# Receiver.net
KiCad netlist of a schematic drawn in EAGLE
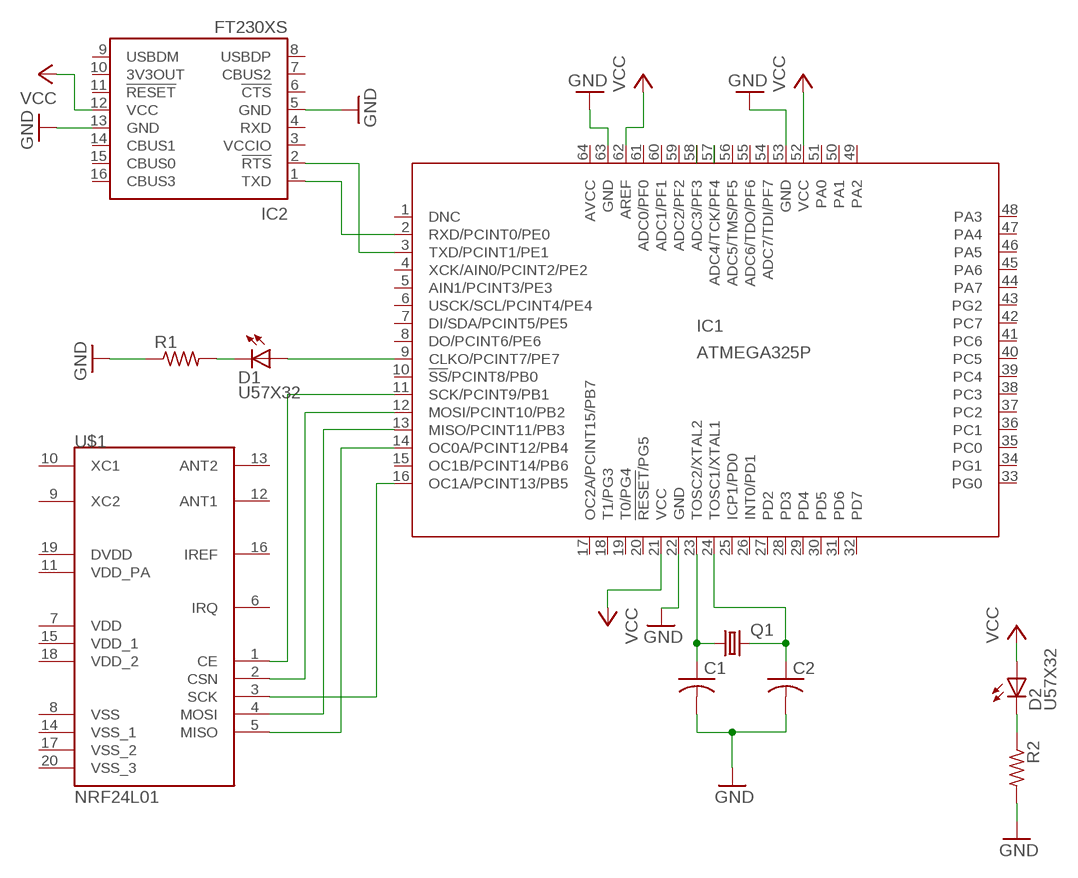
[diagram p0: schematic, sheet 1]

(export (version "E")
  (design (tool "Eeschema 10.0.6"))
  (components
    (comp (ref "C1")
      (value "C-US025-024X044")
      (footprint "eagle-import:C025-024X044")
      (libsource (lib "eagle-import") (part "C-US025-024X044"))
    )
    (comp (ref "C2")
      (value "C-US025-024X044")
      (footprint "eagle-import:C025-024X044")
      (libsource (lib "eagle-import") (part "C-US025-024X044"))
    )
    (comp (ref "D1")
      (value "U57X32")
      (footprint "eagle-import:U57X32")
      (libsource (lib "eagle-import") (part "U57X32"))
    )
    (comp (ref "D2")
      (value "U57X32")
      (footprint "eagle-import:U57X32")
      (libsource (lib "eagle-import") (part "U57X32"))
    )
    (comp (ref "IC1")
      (value "ATMEGA325P")
      (footprint "eagle-import:64M1")
      (fields (field (name "MPN") "ATMEGA325PV-10AU"))
      (libsource (lib "eagle-import") (part "ATMEGA325P"))
    )
    (comp (ref "IC2")
      (value "FT230XS")
      (footprint "eagle-import:SSOP16")
      (libsource (lib "eagle-import") (part "FT230XS"))
    )
    (comp (ref "Q1")
      (value "CRYSTALHC49S")
      (footprint "eagle-import:HC49_S")
      (libsource (lib "eagle-import") (part "CRYSTALHC49S"))
    )
    (comp (ref "R1")
      (value "R-US_0204/5")
      (footprint "eagle-import:0204_5")
      (libsource (lib "eagle-import") (part "R-US_0204/5"))
    )
    (comp (ref "R2")
      (value "R-US_0204/5")
      (footprint "eagle-import:0204_5")
      (libsource (lib "eagle-import") (part "R-US_0204/5"))
    )
    (comp (ref "U$1")
      (value "NRF24L01")
      (footprint "eagle-import:QFN20")
      (libsource (lib "eagle-import") (part "NRF24L01"))
    )
  )
  (nets
    (net (code "1") (name "/AVCC") (class "Default")
      (node (ref "IC1") (pin "64") (pinfunction "AVCC_64") (pintype "power_in"))
    )
    (net (code "2") (name "/VCCIO") (class "Default")
      (node (ref "IC2") (pin "3") (pinfunction "VCCIO_3") (pintype "power_in"))
    )
    (net (code "3") (name "GND") (class "Default")
      (node (ref "C1") (pin "2") (pinfunction "2_2") (pintype "passive"))
      (node (ref "C2") (pin "2") (pinfunction "2_2") (pintype "passive"))
      (node (ref "IC1") (pin "22") (pinfunction "GND_22") (pintype "power_in"))
      (node (ref "IC1") (pin "53") (pinfunction "GND_53") (pintype "power_in"))
      (node (ref "IC1") (pin "63") (pinfunction "GND_63") (pintype "power_in"))
      (node (ref "IC2") (pin "13") (pinfunction "GND_13") (pintype "power_in"))
      (node (ref "IC2") (pin "5") (pinfunction "GND_5") (pintype "power_in"))
      (node (ref "R1") (pin "1") (pinfunction "1_1") (pintype "passive"))
      (node (ref "R2") (pin "2") (pinfunction "2_2") (pintype "passive"))
    )
    (net (code "4") (name "Net-(D1-C)") (class "Default")
      (node (ref "D1") (pin "K") (pinfunction "C_K") (pintype "passive"))
      (node (ref "R1") (pin "2") (pinfunction "2_2") (pintype "passive"))
    )
    (net (code "5") (name "Net-(D2-C)") (class "Default")
      (node (ref "D2") (pin "K") (pinfunction "C_K") (pintype "passive"))
      (node (ref "R2") (pin "1") (pinfunction "1_1") (pintype "passive"))
    )
    (net (code "6") (name "Net-(IC1-CLKO{slash}PCINT7{slash}PE7)") (class "Default")
      (node (ref "D1") (pin "A") (pinfunction "A_A") (pintype "passive"))
      (node (ref "IC1") (pin "9") (pinfunction "CLKO/PCINT7/PE7_9") (pintype "bidirectional"))
    )
    (net (code "7") (name "Net-(IC1-MISO{slash}PCINT11{slash}PB3)") (class "Default")
      (node (ref "IC1") (pin "13") (pinfunction "MISO/PCINT11/PB3_13") (pintype "bidirectional"))
      (node (ref "U$1") (pin "4") (pinfunction "MOSI_4") (pintype "bidirectional"))
    )
    (net (code "8") (name "Net-(IC1-MOSI{slash}PCINT10{slash}PB2)") (class "Default")
      (node (ref "IC1") (pin "12") (pinfunction "MOSI/PCINT10/PB2_12") (pintype "bidirectional"))
      (node (ref "U$1") (pin "2") (pinfunction "CSN_2") (pintype "bidirectional"))
    )
    (net (code "9") (name "Net-(IC1-OC0A{slash}PCINT12{slash}PB4)") (class "Default")
      (node (ref "IC1") (pin "14") (pinfunction "OC0A/PCINT12/PB4_14") (pintype "bidirectional"))
      (node (ref "U$1") (pin "5") (pinfunction "MISO_5") (pintype "bidirectional"))
    )
    (net (code "10") (name "Net-(IC1-OC1A{slash}PCINT13{slash}PB5)") (class "Default")
      (node (ref "IC1") (pin "16") (pinfunction "OC1A/PCINT13/PB5_16") (pintype "bidirectional"))
      (node (ref "U$1") (pin "3") (pinfunction "SCK_3") (pintype "bidirectional"))
    )
    (net (code "11") (name "Net-(IC1-RXD{slash}PCINT0{slash}PE0)") (class "Default")
      (node (ref "IC1") (pin "2") (pinfunction "RXD/PCINT0/PE0_2") (pintype "bidirectional"))
      (node (ref "IC2") (pin "1") (pinfunction "TXD_1") (pintype "output"))
    )
    (net (code "12") (name "Net-(IC1-SCK{slash}PCINT9{slash}PB1)") (class "Default")
      (node (ref "IC1") (pin "11") (pinfunction "SCK/PCINT9/PB1_11") (pintype "bidirectional"))
      (node (ref "U$1") (pin "1") (pinfunction "CE_1") (pintype "bidirectional"))
    )
    (net (code "13") (name "Net-(IC1-TOSC1{slash}XTAL1)") (class "Default")
      (node (ref "C2") (pin "1") (pinfunction "1_1") (pintype "passive"))
      (node (ref "IC1") (pin "24") (pinfunction "TOSC1/XTAL1_24") (pintype "input"))
      (node (ref "Q1") (pin "2") (pinfunction "2_2") (pintype "passive"))
    )
    (net (code "14") (name "Net-(IC1-TOSC2{slash}XTAL2)") (class "Default")
      (node (ref "C1") (pin "1") (pinfunction "1_1") (pintype "passive"))
      (node (ref "IC1") (pin "23") (pinfunction "TOSC2/XTAL2_23") (pintype "output"))
      (node (ref "Q1") (pin "1") (pinfunction "1_1") (pintype "passive"))
    )
    (net (code "15") (name "Net-(IC1-TXD{slash}PCINT1{slash}PE1)") (class "Default")
      (node (ref "IC1") (pin "3") (pinfunction "TXD/PCINT1/PE1_3") (pintype "bidirectional"))
      (node (ref "IC2") (pin "2") (pinfunction "~{RTS}_2") (pintype "output"))
    )
    (net (code "16") (name "VCC") (class "Default")
      (node (ref "D2") (pin "A") (pinfunction "A_A") (pintype "passive"))
      (node (ref "IC1") (pin "21") (pinfunction "VCC_21") (pintype "power_in"))
      (node (ref "IC1") (pin "52") (pinfunction "VCC_52") (pintype "power_in"))
      (node (ref "IC1") (pin "62") (pinfunction "AREF_62") (pintype "input"))
      (node (ref "IC2") (pin "12") (pinfunction "VCC_12") (pintype "power_in"))
    )
    (net (code "17") (name "unconnected-(IC1-ADC0{slash}PF0-Pad61)") (class "Default")
      (node (ref "IC1") (pin "61") (pinfunction "ADC0/PF0_61") (pintype "bidirectional"))
    )
    (net (code "18") (name "unconnected-(IC1-ADC1{slash}PF1-Pad60)") (class "Default")
      (node (ref "IC1") (pin "60") (pinfunction "ADC1/PF1_60") (pintype "bidirectional"))
    )
    (net (code "19") (name "unconnected-(IC1-ADC2{slash}PF2-Pad59)") (class "Default")
      (node (ref "IC1") (pin "59") (pinfunction "ADC2/PF2_59") (pintype "bidirectional"))
    )
    (net (code "20") (name "unconnected-(IC1-ADC3{slash}PF3-Pad58)") (class "Default")
      (node (ref "IC1") (pin "58") (pinfunction "ADC3/PF3_58") (pintype "bidirectional"))
    )
    (net (code "21") (name "unconnected-(IC1-ADC4{slash}TCK{slash}PF4-Pad57)") (class "Default")
      (node (ref "IC1") (pin "57") (pinfunction "ADC4/TCK/PF4_57") (pintype "bidirectional"))
    )
    (net (code "22") (name "unconnected-(IC1-ADC5{slash}TMS{slash}PF5-Pad56)") (class "Default")
      (node (ref "IC1") (pin "56") (pinfunction "ADC5/TMS/PF5_56") (pintype "bidirectional"))
    )
    (net (code "23") (name "unconnected-(IC1-ADC6{slash}TDO{slash}PF6-Pad55)") (class "Default")
      (node (ref "IC1") (pin "55") (pinfunction "ADC6/TDO/PF6_55") (pintype "bidirectional"))
    )
    (net (code "24") (name "unconnected-(IC1-ADC7{slash}TDI{slash}PF7-Pad54)") (class "Default")
      (node (ref "IC1") (pin "54") (pinfunction "ADC7/TDI/PF7_54") (pintype "bidirectional"))
    )
    (net (code "25") (name "unconnected-(IC1-AIN1{slash}PCINT3{slash}PE3-Pad5)") (class "Default")
      (node (ref "IC1") (pin "5") (pinfunction "AIN1/PCINT3/PE3_5") (pintype "bidirectional"))
    )
    (net (code "26") (name "unconnected-(IC1-DI{slash}SDA{slash}PCINT5{slash}PE5-Pad7)") (class "Default")
      (node (ref "IC1") (pin "7") (pinfunction "DI/SDA/PCINT5/PE5_7") (pintype "bidirectional"))
    )
    (net (code "27") (name "unconnected-(IC1-DNC-Pad1)") (class "Default")
      (node (ref "IC1") (pin "1") (pinfunction "DNC_1") (pintype "input"))
    )
    (net (code "28") (name "unconnected-(IC1-DO{slash}PCINT6{slash}PE6-Pad8)") (class "Default")
      (node (ref "IC1") (pin "8") (pinfunction "DO/PCINT6/PE6_8") (pintype "bidirectional"))
    )
    (net (code "29") (name "unconnected-(IC1-ICP1{slash}PD0-Pad25)") (class "Default")
      (node (ref "IC1") (pin "25") (pinfunction "ICP1/PD0_25") (pintype "bidirectional"))
    )
    (net (code "30") (name "unconnected-(IC1-INT0{slash}PD1-Pad26)") (class "Default")
      (node (ref "IC1") (pin "26") (pinfunction "INT0/PD1_26") (pintype "bidirectional"))
    )
    (net (code "31") (name "unconnected-(IC1-OC1B{slash}PCINT14{slash}PB6-Pad15)") (class "Default")
      (node (ref "IC1") (pin "15") (pinfunction "OC1B/PCINT14/PB6_15") (pintype "bidirectional"))
    )
    (net (code "32") (name "unconnected-(IC1-OC2A{slash}PCINT15{slash}PB7-Pad17)") (class "Default")
      (node (ref "IC1") (pin "17") (pinfunction "OC2A/PCINT15/PB7_17") (pintype "bidirectional"))
    )
    (net (code "33") (name "unconnected-(IC1-PA0-Pad51)") (class "Default")
      (node (ref "IC1") (pin "51") (pinfunction "PA0_51") (pintype "bidirectional"))
    )
    (net (code "34") (name "unconnected-(IC1-PA1-Pad50)") (class "Default")
      (node (ref "IC1") (pin "50") (pinfunction "PA1_50") (pintype "bidirectional"))
    )
    (net (code "35") (name "unconnected-(IC1-PA2-Pad49)") (class "Default")
      (node (ref "IC1") (pin "49") (pinfunction "PA2_49") (pintype "bidirectional"))
    )
    (net (code "36") (name "unconnected-(IC1-PA3-Pad48)") (class "Default")
      (node (ref "IC1") (pin "48") (pinfunction "PA3_48") (pintype "bidirectional"))
    )
    (net (code "37") (name "unconnected-(IC1-PA4-Pad47)") (class "Default")
      (node (ref "IC1") (pin "47") (pinfunction "PA4_47") (pintype "bidirectional"))
    )
    (net (code "38") (name "unconnected-(IC1-PA5-Pad46)") (class "Default")
      (node (ref "IC1") (pin "46") (pinfunction "PA5_46") (pintype "bidirectional"))
    )
    (net (code "39") (name "unconnected-(IC1-PA6-Pad45)") (class "Default")
      (node (ref "IC1") (pin "45") (pinfunction "PA6_45") (pintype "bidirectional"))
    )
    (net (code "40") (name "unconnected-(IC1-PA7-Pad44)") (class "Default")
      (node (ref "IC1") (pin "44") (pinfunction "PA7_44") (pintype "bidirectional"))
    )
    (net (code "41") (name "unconnected-(IC1-PC0-Pad35)") (class "Default")
      (node (ref "IC1") (pin "35") (pinfunction "PC0_35") (pintype "bidirectional"))
    )
    (net (code "42") (name "unconnected-(IC1-PC1-Pad36)") (class "Default")
      (node (ref "IC1") (pin "36") (pinfunction "PC1_36") (pintype "bidirectional"))
    )
    (net (code "43") (name "unconnected-(IC1-PC2-Pad37)") (class "Default")
      (node (ref "IC1") (pin "37") (pinfunction "PC2_37") (pintype "bidirectional"))
    )
    (net (code "44") (name "unconnected-(IC1-PC3-Pad38)") (class "Default")
      (node (ref "IC1") (pin "38") (pinfunction "PC3_38") (pintype "bidirectional"))
    )
    (net (code "45") (name "unconnected-(IC1-PC4-Pad39)") (class "Default")
      (node (ref "IC1") (pin "39") (pinfunction "PC4_39") (pintype "bidirectional"))
    )
    (net (code "46") (name "unconnected-(IC1-PC5-Pad40)") (class "Default")
      (node (ref "IC1") (pin "40") (pinfunction "PC5_40") (pintype "bidirectional"))
    )
    (net (code "47") (name "unconnected-(IC1-PC6-Pad41)") (class "Default")
      (node (ref "IC1") (pin "41") (pinfunction "PC6_41") (pintype "bidirectional"))
    )
    (net (code "48") (name "unconnected-(IC1-PC7-Pad42)") (class "Default")
      (node (ref "IC1") (pin "42") (pinfunction "PC7_42") (pintype "bidirectional"))
    )
    (net (code "49") (name "unconnected-(IC1-PD2-Pad27)") (class "Default")
      (node (ref "IC1") (pin "27") (pinfunction "PD2_27") (pintype "bidirectional"))
    )
    (net (code "50") (name "unconnected-(IC1-PD3-Pad28)") (class "Default")
      (node (ref "IC1") (pin "28") (pinfunction "PD3_28") (pintype "bidirectional"))
    )
    (net (code "51") (name "unconnected-(IC1-PD4-Pad29)") (class "Default")
      (node (ref "IC1") (pin "29") (pinfunction "PD4_29") (pintype "bidirectional"))
    )
    (net (code "52") (name "unconnected-(IC1-PD5-Pad30)") (class "Default")
      (node (ref "IC1") (pin "30") (pinfunction "PD5_30") (pintype "bidirectional"))
    )
    (net (code "53") (name "unconnected-(IC1-PD6-Pad31)") (class "Default")
      (node (ref "IC1") (pin "31") (pinfunction "PD6_31") (pintype "bidirectional"))
    )
    (net (code "54") (name "unconnected-(IC1-PD7-Pad32)") (class "Default")
      (node (ref "IC1") (pin "32") (pinfunction "PD7_32") (pintype "bidirectional"))
    )
    (net (code "55") (name "unconnected-(IC1-PG0-Pad33)") (class "Default")
      (node (ref "IC1") (pin "33") (pinfunction "PG0_33") (pintype "bidirectional"))
    )
    (net (code "56") (name "unconnected-(IC1-PG1-Pad34)") (class "Default")
      (node (ref "IC1") (pin "34") (pinfunction "PG1_34") (pintype "bidirectional"))
    )
    (net (code "57") (name "unconnected-(IC1-PG2-Pad43)") (class "Default")
      (node (ref "IC1") (pin "43") (pinfunction "PG2_43") (pintype "bidirectional"))
    )
    (net (code "58") (name "unconnected-(IC1-T0{slash}PG4-Pad19)") (class "Default")
      (node (ref "IC1") (pin "19") (pinfunction "T0/PG4_19") (pintype "bidirectional"))
    )
    (net (code "59") (name "unconnected-(IC1-T1{slash}PG3-Pad18)") (class "Default")
      (node (ref "IC1") (pin "18") (pinfunction "T1/PG3_18") (pintype "bidirectional"))
    )
    (net (code "60") (name "unconnected-(IC1-USCK{slash}SCL{slash}PCINT4{slash}PE4-Pad6)") (class "Default")
      (node (ref "IC1") (pin "6") (pinfunction "USCK/SCL/PCINT4/PE4_6") (pintype "bidirectional"))
    )
    (net (code "61") (name "unconnected-(IC1-XCK{slash}AIN0{slash}PCINT2{slash}PE2-Pad4)") (class "Default")
      (node (ref "IC1") (pin "4") (pinfunction "XCK/AIN0/PCINT2/PE2_4") (pintype "bidirectional"))
    )
    (net (code "62") (name "unconnected-(IC1-~{RESET}{slash}PG5-Pad20)") (class "Default")
      (node (ref "IC1") (pin "20") (pinfunction "~{RESET}/PG5_20") (pintype "input"))
    )
    (net (code "63") (name "unconnected-(IC1-~{SS}{slash}PCINT8{slash}PB0-Pad10)") (class "Default")
      (node (ref "IC1") (pin "10") (pinfunction "~{SS}/PCINT8/PB0_10") (pintype "bidirectional"))
    )
    (net (code "64") (name "unconnected-(IC2-3V3OUT-Pad10)") (class "Default")
      (node (ref "IC2") (pin "10") (pinfunction "3V3OUT_10") (pintype "output"))
    )
    (net (code "65") (name "unconnected-(IC2-CBUS0-Pad15)") (class "Default")
      (node (ref "IC2") (pin "15") (pinfunction "CBUS0_15") (pintype "bidirectional"))
    )
    (net (code "66") (name "unconnected-(IC2-CBUS1-Pad14)") (class "Default")
      (node (ref "IC2") (pin "14") (pinfunction "CBUS1_14") (pintype "bidirectional"))
    )
    (net (code "67") (name "unconnected-(IC2-CBUS2-Pad7)") (class "Default")
      (node (ref "IC2") (pin "7") (pinfunction "CBUS2_7") (pintype "bidirectional"))
    )
    (net (code "68") (name "unconnected-(IC2-CBUS3-Pad16)") (class "Default")
      (node (ref "IC2") (pin "16") (pinfunction "CBUS3_16") (pintype "bidirectional"))
    )
    (net (code "69") (name "unconnected-(IC2-RXD-Pad4)") (class "Default")
      (node (ref "IC2") (pin "4") (pinfunction "RXD_4") (pintype "input"))
    )
    (net (code "70") (name "unconnected-(IC2-USBDM-Pad9)") (class "Default")
      (node (ref "IC2") (pin "9") (pinfunction "USBDM_9") (pintype "input"))
    )
    (net (code "71") (name "unconnected-(IC2-USBDP-Pad8)") (class "Default")
      (node (ref "IC2") (pin "8") (pinfunction "USBDP_8") (pintype "input"))
    )
    (net (code "72") (name "unconnected-(IC2-~{CTS}-Pad6)") (class "Default")
      (node (ref "IC2") (pin "6") (pinfunction "~{CTS}_6") (pintype "input"))
    )
    (net (code "73") (name "unconnected-(IC2-~{RESET}-Pad11)") (class "Default")
      (node (ref "IC2") (pin "11") (pinfunction "~{RESET}_11") (pintype "input"))
    )
    (net (code "74") (name "unconnected-(U$1-ANT1-Pad12)") (class "Default")
      (node (ref "U$1") (pin "12") (pinfunction "ANT1_12") (pintype "bidirectional"))
    )
    (net (code "75") (name "unconnected-(U$1-ANT2-Pad13)") (class "Default")
      (node (ref "U$1") (pin "13") (pinfunction "ANT2_13") (pintype "bidirectional"))
    )
    (net (code "76") (name "unconnected-(U$1-DVDD-Pad19)") (class "Default")
      (node (ref "U$1") (pin "19") (pinfunction "DVDD_19") (pintype "bidirectional"))
    )
    (net (code "77") (name "unconnected-(U$1-IREF-Pad16)") (class "Default")
      (node (ref "U$1") (pin "16") (pinfunction "IREF_16") (pintype "bidirectional"))
    )
    (net (code "78") (name "unconnected-(U$1-IRQ-Pad6)") (class "Default")
      (node (ref "U$1") (pin "6") (pinfunction "IRQ_6") (pintype "bidirectional"))
    )
    (net (code "79") (name "unconnected-(U$1-VDD-Pad7)") (class "Default")
      (node (ref "U$1") (pin "7") (pinfunction "VDD_7") (pintype "bidirectional"))
    )
    (net (code "80") (name "unconnected-(U$1-VDD_1-Pad15)") (class "Default")
      (node (ref "U$1") (pin "15") (pinfunction "VDD_1_15") (pintype "bidirectional"))
    )
    (net (code "81") (name "unconnected-(U$1-VDD_2-Pad18)") (class "Default")
      (node (ref "U$1") (pin "18") (pinfunction "VDD_2_18") (pintype "bidirectional"))
    )
    (net (code "82") (name "unconnected-(U$1-VDD_PA-Pad11)") (class "Default")
      (node (ref "U$1") (pin "11") (pinfunction "VDD_PA_11") (pintype "bidirectional"))
    )
    (net (code "83") (name "unconnected-(U$1-VSS-Pad8)") (class "Default")
      (node (ref "U$1") (pin "8") (pinfunction "VSS_8") (pintype "bidirectional"))
    )
    (net (code "84") (name "unconnected-(U$1-VSS_1-Pad14)") (class "Default")
      (node (ref "U$1") (pin "14") (pinfunction "VSS_1_14") (pintype "bidirectional"))
    )
    (net (code "85") (name "unconnected-(U$1-VSS_2-Pad17)") (class "Default")
      (node (ref "U$1") (pin "17") (pinfunction "VSS_2_17") (pintype "bidirectional"))
    )
    (net (code "86") (name "unconnected-(U$1-VSS_3-Pad20)") (class "Default")
      (node (ref "U$1") (pin "20") (pinfunction "VSS_3_20") (pintype "bidirectional"))
    )
    (net (code "87") (name "unconnected-(U$1-XC1-Pad10)") (class "Default")
      (node (ref "U$1") (pin "10") (pinfunction "XC1_10") (pintype "bidirectional"))
    )
    (net (code "88") (name "unconnected-(U$1-XC2-Pad9)") (class "Default")
      (node (ref "U$1") (pin "9") (pinfunction "XC2_9") (pintype "bidirectional"))
    )
  )
)
